# Ver_1.net
KiCad netlist of a schematic drawn in Altium Designer
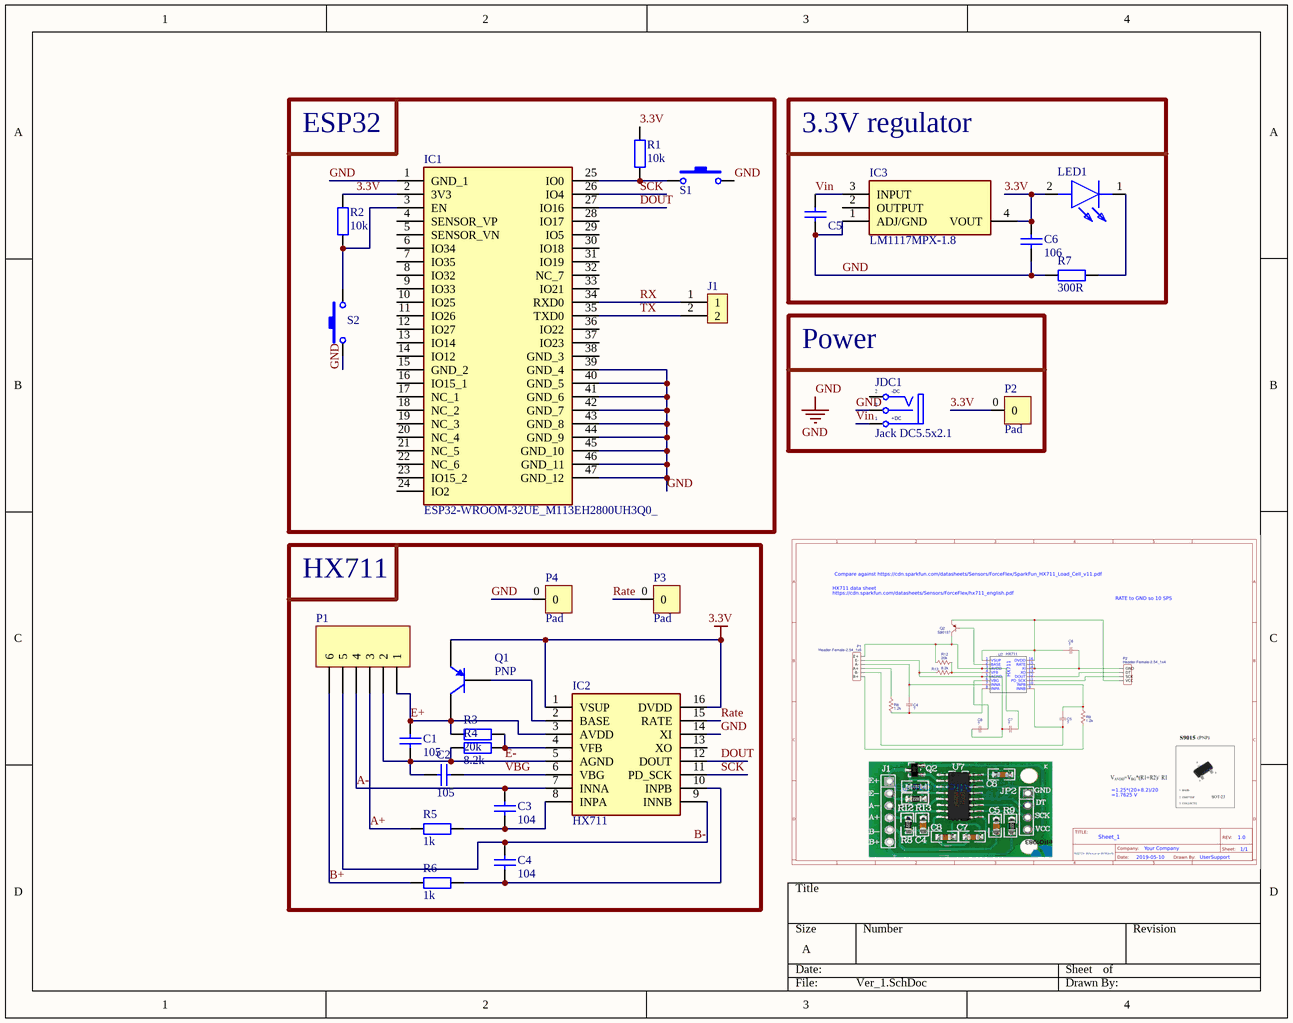
[diagram p0: Ver_1.SchDoc]

(export (version "E")
  (design (tool "Eeschema 10.0.6"))
  (components
    (comp (ref "C1")
      (value "105")
      (footprint "Tu 0805")
      (description "Dán")
      (libsource (lib "THU VIEN SCH") (part "Tu 105"))
    )
    (comp (ref "C2")
      (value "105")
      (footprint "Tu 0805")
      (description "Dán")
      (libsource (lib "THU VIEN SCH") (part "Tu 105"))
    )
    (comp (ref "C3")
      (value "104")
      (footprint "Tu 0805")
      (description "Dán")
      (libsource (lib "THU VIEN SCH") (part "Tu 104"))
    )
    (comp (ref "C4")
      (value "104")
      (footprint "Tu 0805")
      (description "Dán")
      (libsource (lib "THU VIEN SCH") (part "Tu 104"))
    )
    (comp (ref "C5")
      (value "106")
      (footprint "Tu 0805")
      (description "Dán")
      (libsource (lib "THU VIEN SCH") (part "Tu 106"))
    )
    (comp (ref "C6")
      (value "106")
      (footprint "Tu 0805")
      (description "Dán")
      (libsource (lib "THU VIEN SCH") (part "Tu 0805 106 16V 10%"))
    )
    (comp (ref "IC1")
      (value "ESP32-WROOM-32UE_M113EH2800UH3Q0_")
      (footprint "SamacSys:ESP32WROOM32UEM113EH2800UH3Q0")
      (description "Integrated Circuit")
      (fields (field (name "MANUFACTURER_PART_NUMBER") "ESP32-WROOM-32UE(M113EH2800UH3Q0)"))
      (libsource (lib "SamacSys") (part "ESP32-WROOM-32UE_M113EH2800UH3Q0_"))
    )
    (comp (ref "IC2")
      (value "HX711")
      (footprint "SamacSys:SOIC127P600X160-16N")
      (description "Integrated Circuit")
      (libsource (lib "SamacSys") (part "HX711"))
    )
    (comp (ref "IC3")
      (value "LM1117MPX-1.8")
      (footprint "SamacSys:SOT230P700X180-4N")
      (description "Integrated Circuit")
      (fields (field (name "MOUSER PART NUMBER") "926-LM1117MPX-18"))
      (libsource (lib "SamacSys") (part "LM1117MPX-1.8"))
    )
    (comp (ref "J1")
      (value "jump don duc 2.54_2p")
      (footprint "jump don duc_2p")
      (libsource (lib "THU VIEN SCH") (part "jump don duc 2.54_2p"))
    )
    (comp (ref "JDC1")
      (value "Jack DC5.5x2.1")
      (footprint "DC-IN")
      (description "Cắm")
      (libsource (lib "THU VIEN SCH") (part "Jac_DC"))
    )
    (comp (ref "LED1")
      (value "SML-LXT0805GW-TR")
      (footprint "SamacSys:LEDC2012X80N")
      (description "LED")
      (fields (field (name "MOUSER PART NUMBER") "696-SML-LXT0805GW"))
      (libsource (lib "SamacSys") (part "SML-LXT0805GW-TR"))
    )
    (comp (ref "P1")
      (value "Header 6")
      (footprint "HDR1X6")
      (description "Header, 6-Pin")
      (fields (field (name "PUBLISHER") "Altium Limited"))
      (libsource (lib "Miscellaneous Connectors") (part "Header 6"))
    )
    (comp (ref "P2") (value "Pad") (footprint "Pad") (libsource (lib "SamacSys") (part "Pad")))
    (comp (ref "P3") (value "Pad") (footprint "Pad") (libsource (lib "SamacSys") (part "Pad")))
    (comp (ref "P4") (value "Pad") (footprint "Pad") (libsource (lib "SamacSys") (part "Pad")))
    (comp (ref "Q1")
      (value "PNP")
      (footprint "SOT-23B_N")
      (description "PNP Bipolar Transistor")
      (fields (field (name "PUBLISHER") "Altium Limited"))
      (libsource (lib "Miscellaneous Devices") (part "PNP"))
    )
    (comp (ref "R1")
      (value "10k")
      (footprint "tro smd 0805")
      (description "Dán")
      (libsource (lib "THU VIEN SCH") (part "Tro 0805 1% 10k"))
    )
    (comp (ref "R2")
      (value "10k")
      (footprint "tro smd 0805")
      (description "Dán")
      (libsource (lib "THU VIEN SCH") (part "Tro 0805 1% 10k"))
    )
    (comp (ref "R3")
      (value "20k")
      (footprint "tro smd 0805")
      (description "Dán")
      (libsource (lib "THU VIEN SCH") (part "Tro 0805 5% 20k"))
    )
    (comp (ref "R4")
      (value "8.2k")
      (footprint "tro smd 0805")
      (description "Dán")
      (libsource (lib "THU VIEN SCH") (part "Tro 0805 5% 8.2k"))
    )
    (comp (ref "R5")
      (value "1k")
      (footprint "tro smd 0805")
      (description "Dán")
      (libsource (lib "THU VIEN SCH") (part "Tro 0805 5% 1k"))
    )
    (comp (ref "R6")
      (value "1k")
      (footprint "tro smd 0805")
      (description "Dán")
      (libsource (lib "THU VIEN SCH") (part "Tro 0805 5% 1k"))
    )
    (comp (ref "R7")
      (value "300R")
      (footprint "Tro SMD 0805")
      (description "Dán")
      (libsource (lib "THU VIEN SCH") (part "Tro 0805 5% 300R"))
    )
    (comp (ref "S1")
      (value "MH001036")
      (footprint "SW-SMD")
      (description "Dán")
      (libsource (lib "THU VIEN SCH") (part "SW-SMD"))
    )
    (comp (ref "S2")
      (value "MH001036")
      (footprint "SW-SMD")
      (description "Dán")
      (libsource (lib "THU VIEN SCH") (part "SW-SMD"))
    )
  )
  (nets
    (net (code "1") (name "/A+") (class "Default")
      (node (ref "P1") (pin "3") (pinfunction "3_3") (pintype "passive"))
      (node (ref "R5") (pin "1") (pinfunction "1_1") (pintype "passive"))
    )
    (net (code "2") (name "/A-") (class "Default")
      (node (ref "C3") (pin "2") (pinfunction "2_2") (pintype "passive"))
      (node (ref "IC2") (pin "7") (pinfunction "INNA_7") (pintype "passive"))
      (node (ref "P1") (pin "4") (pinfunction "4_4") (pintype "passive"))
    )
    (net (code "3") (name "/B+") (class "Default")
      (node (ref "P1") (pin "6") (pinfunction "6_6") (pintype "passive"))
      (node (ref "R6") (pin "1") (pinfunction "1_1") (pintype "passive"))
    )
    (net (code "4") (name "/B-") (class "Default")
      (node (ref "C4") (pin "2") (pinfunction "2_2") (pintype "passive"))
      (node (ref "IC2") (pin "9") (pinfunction "INNB_9") (pintype "passive"))
      (node (ref "P1") (pin "5") (pinfunction "5_5") (pintype "passive"))
    )
    (net (code "5") (name "/DOUT") (class "Default")
      (node (ref "IC1") (pin "27") (pinfunction "IO16_27") (pintype "passive"))
      (node (ref "IC2") (pin "12") (pinfunction "DOUT_12") (pintype "passive"))
    )
    (net (code "6") (name "/E+") (class "Default")
      (node (ref "C1") (pin "2") (pinfunction "2_2") (pintype "passive"))
      (node (ref "IC2") (pin "3") (pinfunction "AVDD_3") (pintype "passive"))
      (node (ref "P1") (pin "1") (pinfunction "1_1") (pintype "passive"))
      (node (ref "Q1") (pin "1") (pinfunction "C_1") (pintype "passive"))
      (node (ref "R3") (pin "1") (pinfunction "1_1") (pintype "passive"))
    )
    (net (code "7") (name "/E-") (class "Default")
      (node (ref "C1") (pin "1") (pinfunction "1_1") (pintype "passive"))
      (node (ref "C2") (pin "1") (pinfunction "1_1") (pintype "passive"))
      (node (ref "IC2") (pin "5") (pinfunction "AGND_5") (pintype "passive"))
      (node (ref "P1") (pin "2") (pinfunction "2_2") (pintype "passive"))
      (node (ref "R4") (pin "1") (pinfunction "1_1") (pintype "passive"))
    )
    (net (code "8") (name "/RX") (class "Default")
      (node (ref "IC1") (pin "34") (pinfunction "RXD0_34") (pintype "passive"))
      (node (ref "J1") (pin "1") (pinfunction "1_1") (pintype "passive"))
    )
    (net (code "9") (name "/Rate") (class "Default")
      (node (ref "IC2") (pin "15") (pinfunction "RATE_15") (pintype "passive"))
      (node (ref "P3") (pin "0") (pinfunction "0_0") (pintype "passive"))
    )
    (net (code "10") (name "/SCK") (class "Default")
      (node (ref "IC1") (pin "26") (pinfunction "IO4_26") (pintype "passive"))
      (node (ref "IC2") (pin "11") (pinfunction "PD_SCK_11") (pintype "passive"))
    )
    (net (code "11") (name "/TX") (class "Default")
      (node (ref "IC1") (pin "35") (pinfunction "TXD0_35") (pintype "passive"))
      (node (ref "J1") (pin "2") (pinfunction "2_2") (pintype "passive"))
    )
    (net (code "12") (name "/VBG") (class "Default")
      (node (ref "C2") (pin "2") (pinfunction "2_2") (pintype "passive"))
      (node (ref "IC2") (pin "6") (pinfunction "VBG_6") (pintype "passive"))
    )
    (net (code "13") (name "/Vin") (class "Default")
      (node (ref "C5") (pin "2") (pinfunction "2_2") (pintype "passive"))
      (node (ref "IC3") (pin "3") (pinfunction "INPUT_3") (pintype "passive"))
      (node (ref "JDC1") (pin "1") (pinfunction "T_1") (pintype "passive"))
    )
    (net (code "14") (name "3.3V") (class "Default")
      (node (ref "C6") (pin "1") (pinfunction "1_1") (pintype "passive"))
      (node (ref "IC1") (pin "2") (pinfunction "3V3_2") (pintype "passive"))
      (node (ref "IC2") (pin "1") (pinfunction "VSUP_1") (pintype "passive"))
      (node (ref "IC2") (pin "16") (pinfunction "DVDD_16") (pintype "passive"))
      (node (ref "IC3") (pin "4") (pinfunction "VOUT_4") (pintype "passive"))
      (node (ref "LED1") (pin "2") (pinfunction "A_2") (pintype "passive"))
      (node (ref "P2") (pin "0") (pinfunction "0_0") (pintype "passive"))
      (node (ref "Q1") (pin "3") (pinfunction "E_3") (pintype "passive"))
      (node (ref "R1") (pin "2") (pinfunction "2_2") (pintype "passive"))
      (node (ref "R2") (pin "2") (pinfunction "2_2") (pintype "passive"))
    )
    (net (code "15") (name "GND") (class "Default")
      (node (ref "C5") (pin "1") (pinfunction "1_1") (pintype "passive"))
      (node (ref "C6") (pin "2") (pinfunction "2_2") (pintype "passive"))
      (node (ref "IC1") (pin "1") (pinfunction "GND_1_1") (pintype "passive"))
      (node (ref "IC1") (pin "39") (pinfunction "GND_4_39") (pintype "passive"))
      (node (ref "IC1") (pin "40") (pinfunction "GND_5_40") (pintype "passive"))
      (node (ref "IC1") (pin "41") (pinfunction "GND_6_41") (pintype "passive"))
      (node (ref "IC1") (pin "42") (pinfunction "GND_7_42") (pintype "passive"))
      (node (ref "IC1") (pin "43") (pinfunction "GND_8_43") (pintype "passive"))
      (node (ref "IC1") (pin "44") (pinfunction "GND_9_44") (pintype "passive"))
      (node (ref "IC1") (pin "45") (pinfunction "GND_10_45") (pintype "passive"))
      (node (ref "IC1") (pin "46") (pinfunction "GND_11_46") (pintype "passive"))
      (node (ref "IC1") (pin "47") (pinfunction "GND_12_47") (pintype "passive"))
      (node (ref "IC2") (pin "14") (pinfunction "XI_14") (pintype "passive"))
      (node (ref "IC3") (pin "1") (pinfunction "ADJ/GND_1") (pintype "passive"))
      (node (ref "JDC1") (pin "3") (pinfunction "S_3") (pintype "power_in"))
      (node (ref "P4") (pin "0") (pinfunction "0_0") (pintype "passive"))
      (node (ref "R7") (pin "1") (pinfunction "1_1") (pintype "passive"))
      (node (ref "S1") (pin "1") (pinfunction "1_1") (pintype "passive"))
      (node (ref "S2") (pin "1") (pinfunction "1_1") (pintype "passive"))
    )
    (net (code "16") (name "Net-(IC1-EN)") (class "Default")
      (node (ref "IC1") (pin "3") (pinfunction "EN_3") (pintype "passive"))
      (node (ref "R2") (pin "1") (pinfunction "1_1") (pintype "passive"))
      (node (ref "S2") (pin "2") (pinfunction "2_2") (pintype "passive"))
    )
    (net (code "17") (name "Net-(IC1-IO0)") (class "Default")
      (node (ref "IC1") (pin "25") (pinfunction "IO0_25") (pintype "passive"))
      (node (ref "R1") (pin "1") (pinfunction "1_1") (pintype "passive"))
      (node (ref "S1") (pin "2") (pinfunction "2_2") (pintype "passive"))
    )
    (net (code "18") (name "Net-(IC2-BASE)") (class "Default")
      (node (ref "IC2") (pin "2") (pinfunction "BASE_2") (pintype "passive"))
      (node (ref "Q1") (pin "2") (pinfunction "B_2") (pintype "passive"))
    )
    (net (code "19") (name "Net-(IC2-INPA)") (class "Default")
      (node (ref "C3") (pin "1") (pinfunction "1_1") (pintype "passive"))
      (node (ref "IC2") (pin "8") (pinfunction "INPA_8") (pintype "passive"))
      (node (ref "R5") (pin "2") (pinfunction "2_2") (pintype "passive"))
    )
    (net (code "20") (name "Net-(IC2-INPB)") (class "Default")
      (node (ref "C4") (pin "1") (pinfunction "1_1") (pintype "passive"))
      (node (ref "IC2") (pin "10") (pinfunction "INPB_10") (pintype "passive"))
      (node (ref "R6") (pin "2") (pinfunction "2_2") (pintype "passive"))
    )
    (net (code "21") (name "Net-(IC2-VFB)") (class "Default")
      (node (ref "IC2") (pin "4") (pinfunction "VFB_4") (pintype "passive"))
      (node (ref "R3") (pin "2") (pinfunction "2_2") (pintype "passive"))
      (node (ref "R4") (pin "2") (pinfunction "2_2") (pintype "passive"))
    )
    (net (code "22") (name "Net-(LED1-K)") (class "Default")
      (node (ref "LED1") (pin "1") (pinfunction "K_1") (pintype "passive"))
      (node (ref "R7") (pin "2") (pinfunction "2_2") (pintype "passive"))
    )
    (net (code "23") (name "unconnected-(IC1-GND_2-Pad15)") (class "Default")
      (node (ref "IC1") (pin "15") (pinfunction "GND_2_15") (pintype "passive"))
    )
    (net (code "24") (name "unconnected-(IC1-GND_3-Pad38)") (class "Default")
      (node (ref "IC1") (pin "38") (pinfunction "GND_3_38") (pintype "passive"))
    )
    (net (code "25") (name "unconnected-(IC1-IO2-Pad24)") (class "Default")
      (node (ref "IC1") (pin "24") (pinfunction "IO2_24") (pintype "passive"))
    )
    (net (code "26") (name "unconnected-(IC1-IO5-Pad29)") (class "Default")
      (node (ref "IC1") (pin "29") (pinfunction "IO5_29") (pintype "passive"))
    )
    (net (code "27") (name "unconnected-(IC1-IO12-Pad14)") (class "Default")
      (node (ref "IC1") (pin "14") (pinfunction "IO12_14") (pintype "passive"))
    )
    (net (code "28") (name "unconnected-(IC1-IO14-Pad13)") (class "Default")
      (node (ref "IC1") (pin "13") (pinfunction "IO14_13") (pintype "passive"))
    )
    (net (code "29") (name "unconnected-(IC1-IO15_1-Pad16)") (class "Default")
      (node (ref "IC1") (pin "16") (pinfunction "IO15_1_16") (pintype "passive"))
    )
    (net (code "30") (name "unconnected-(IC1-IO15_2-Pad23)") (class "Default")
      (node (ref "IC1") (pin "23") (pinfunction "IO15_2_23") (pintype "passive"))
    )
    (net (code "31") (name "unconnected-(IC1-IO17-Pad28)") (class "Default")
      (node (ref "IC1") (pin "28") (pinfunction "IO17_28") (pintype "passive"))
    )
    (net (code "32") (name "unconnected-(IC1-IO18-Pad30)") (class "Default")
      (node (ref "IC1") (pin "30") (pinfunction "IO18_30") (pintype "passive"))
    )
    (net (code "33") (name "unconnected-(IC1-IO19-Pad31)") (class "Default")
      (node (ref "IC1") (pin "31") (pinfunction "IO19_31") (pintype "passive"))
    )
    (net (code "34") (name "unconnected-(IC1-IO21-Pad33)") (class "Default")
      (node (ref "IC1") (pin "33") (pinfunction "IO21_33") (pintype "passive"))
    )
    (net (code "35") (name "unconnected-(IC1-IO22-Pad36)") (class "Default")
      (node (ref "IC1") (pin "36") (pinfunction "IO22_36") (pintype "passive"))
    )
    (net (code "36") (name "unconnected-(IC1-IO23-Pad37)") (class "Default")
      (node (ref "IC1") (pin "37") (pinfunction "IO23_37") (pintype "passive"))
    )
    (net (code "37") (name "unconnected-(IC1-IO25-Pad10)") (class "Default")
      (node (ref "IC1") (pin "10") (pinfunction "IO25_10") (pintype "passive"))
    )
    (net (code "38") (name "unconnected-(IC1-IO26-Pad11)") (class "Default")
      (node (ref "IC1") (pin "11") (pinfunction "IO26_11") (pintype "passive"))
    )
    (net (code "39") (name "unconnected-(IC1-IO27-Pad12)") (class "Default")
      (node (ref "IC1") (pin "12") (pinfunction "IO27_12") (pintype "passive"))
    )
    (net (code "40") (name "unconnected-(IC1-IO32-Pad8)") (class "Default")
      (node (ref "IC1") (pin "8") (pinfunction "IO32_8") (pintype "passive"))
    )
    (net (code "41") (name "unconnected-(IC1-IO33-Pad9)") (class "Default")
      (node (ref "IC1") (pin "9") (pinfunction "IO33_9") (pintype "passive"))
    )
    (net (code "42") (name "unconnected-(IC1-IO34-Pad6)") (class "Default")
      (node (ref "IC1") (pin "6") (pinfunction "IO34_6") (pintype "passive"))
    )
    (net (code "43") (name "unconnected-(IC1-IO35-Pad7)") (class "Default")
      (node (ref "IC1") (pin "7") (pinfunction "IO35_7") (pintype "passive"))
    )
    (net (code "44") (name "unconnected-(IC1-NC_1-Pad17)") (class "Default")
      (node (ref "IC1") (pin "17") (pinfunction "NC_1_17") (pintype "passive"))
    )
    (net (code "45") (name "unconnected-(IC1-NC_2-Pad18)") (class "Default")
      (node (ref "IC1") (pin "18") (pinfunction "NC_2_18") (pintype "passive"))
    )
    (net (code "46") (name "unconnected-(IC1-NC_3-Pad19)") (class "Default")
      (node (ref "IC1") (pin "19") (pinfunction "NC_3_19") (pintype "passive"))
    )
    (net (code "47") (name "unconnected-(IC1-NC_4-Pad20)") (class "Default")
      (node (ref "IC1") (pin "20") (pinfunction "NC_4_20") (pintype "passive"))
    )
    (net (code "48") (name "unconnected-(IC1-NC_5-Pad21)") (class "Default")
      (node (ref "IC1") (pin "21") (pinfunction "NC_5_21") (pintype "passive"))
    )
    (net (code "49") (name "unconnected-(IC1-NC_6-Pad22)") (class "Default")
      (node (ref "IC1") (pin "22") (pinfunction "NC_6_22") (pintype "passive"))
    )
    (net (code "50") (name "unconnected-(IC1-NC_7-Pad32)") (class "Default")
      (node (ref "IC1") (pin "32") (pinfunction "NC_7_32") (pintype "passive"))
    )
    (net (code "51") (name "unconnected-(IC1-SENSOR_VN-Pad5)") (class "Default")
      (node (ref "IC1") (pin "5") (pinfunction "SENSOR_VN_5") (pintype "passive"))
    )
    (net (code "52") (name "unconnected-(IC1-SENSOR_VP-Pad4)") (class "Default")
      (node (ref "IC1") (pin "4") (pinfunction "SENSOR_VP_4") (pintype "passive"))
    )
    (net (code "53") (name "unconnected-(IC2-XO-Pad13)") (class "Default")
      (node (ref "IC2") (pin "13") (pinfunction "XO_13") (pintype "passive"))
    )
    (net (code "54") (name "unconnected-(IC3-OUTPUT-Pad2)") (class "Default")
      (node (ref "IC3") (pin "2") (pinfunction "OUTPUT_2") (pintype "passive"))
    )
    (net (code "55") (name "unconnected-(JDC1-TN-Pad2)") (class "Default")
      (node (ref "JDC1") (pin "2") (pinfunction "TN_2") (pintype "passive"))
    )
  )
)
